# VisualightMicroDIY_034_gnd.net
KiCad netlist of a schematic drawn in EAGLE
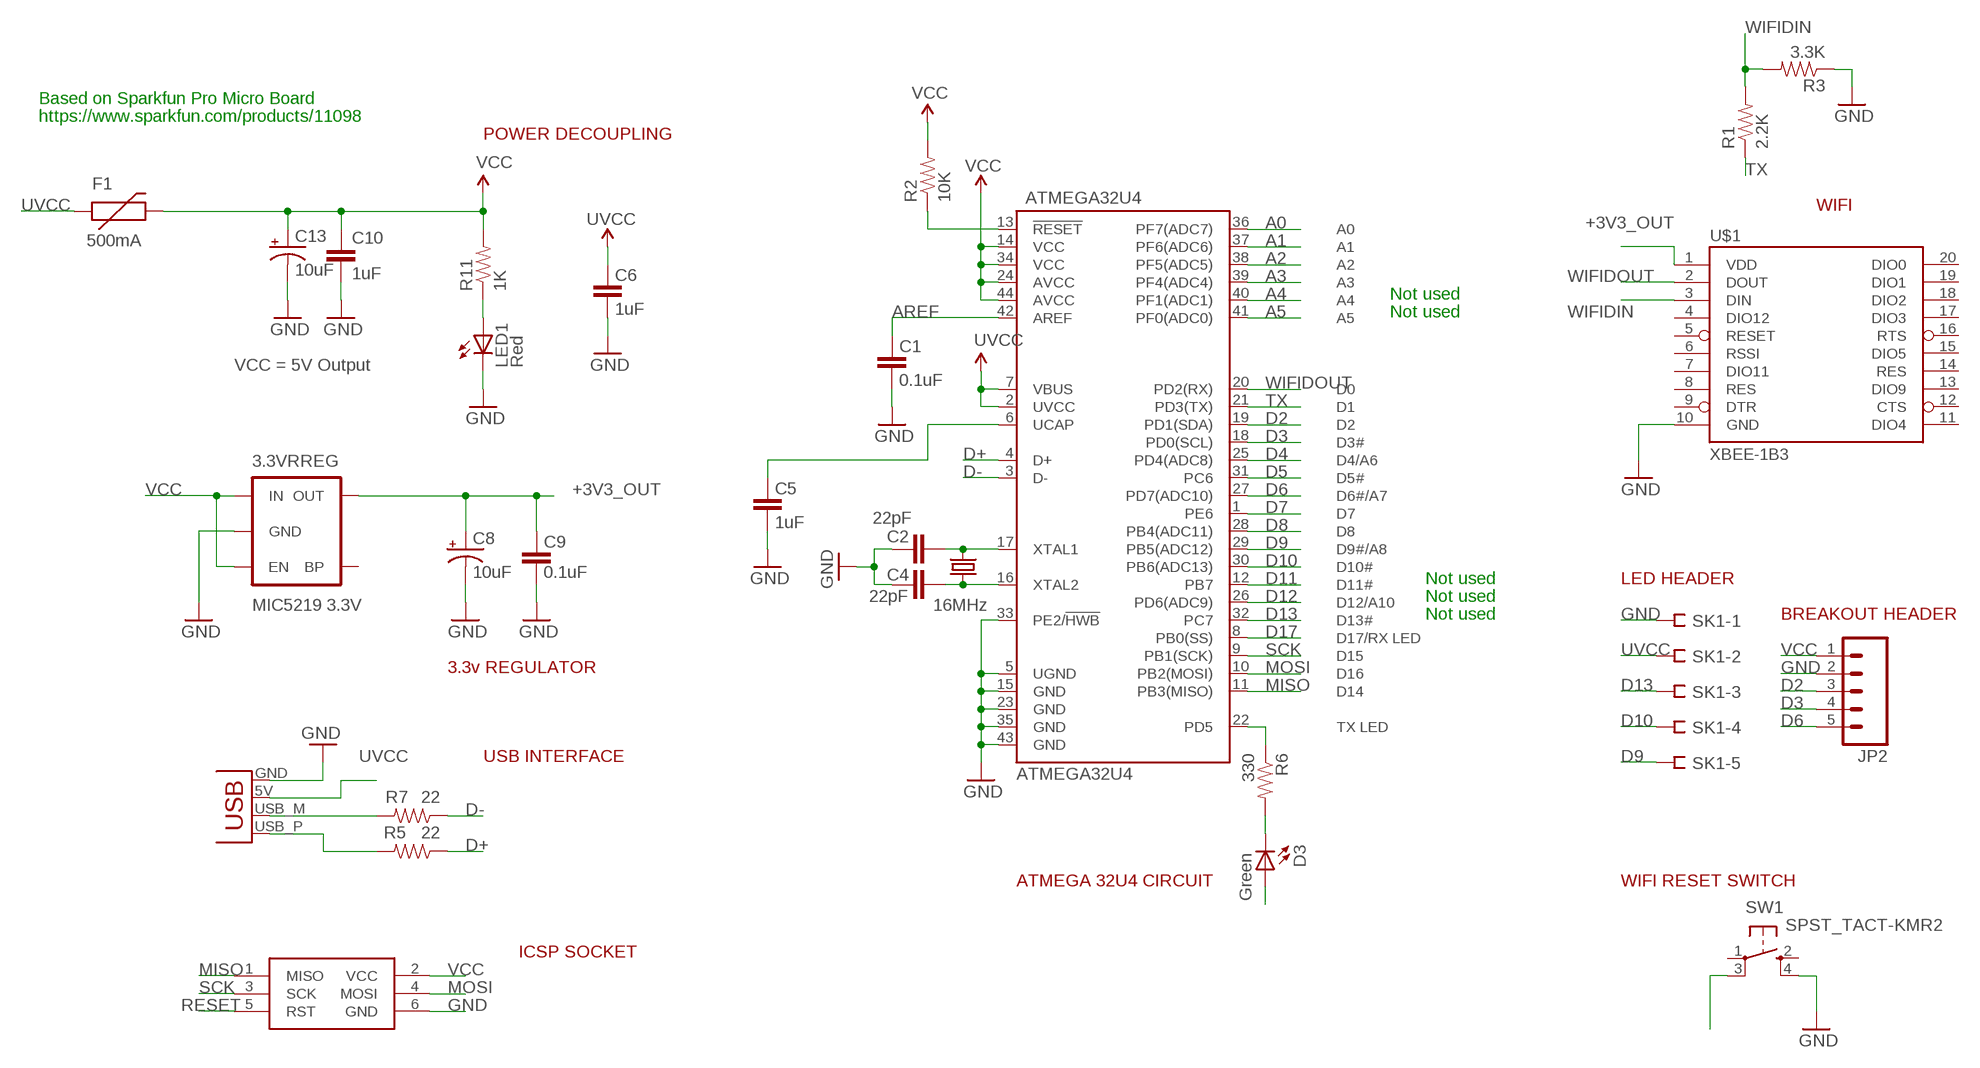
[diagram p0: schematic, sheet 1]

(export (version "E")
  (design (tool "Eeschema 10.0.6"))
  (components
    (comp (ref "3.3VRREG")
      (value "MIC5219 3.3V")
      (footprint "eagle-import:SOT23-5")
      (libsource (lib "eagle-import") (part "V_REG_MIC52193.3V"))
    )
    (comp (ref "ATMEGA32U4")
      (value "ATMEGA32U4")
      (footprint "eagle-import:SPARKFUN-DIGITALIC_TQFP44")
      (libsource (lib "eagle-import") (part "ATMEGA32U4TQFP"))
    )
    (comp (ref "C1")
      (value "0.1uF")
      (footprint "eagle-import:0402-CAP")
      (libsource (lib "eagle-import") (part "CAP0402-CAP"))
    )
    (comp (ref "C2")
      (value "22pF")
      (footprint "eagle-import:0402-CAP")
      (libsource (lib "eagle-import") (part "CAP0402-CAP"))
    )
    (comp (ref "C4")
      (value "22pF")
      (footprint "eagle-import:0402-CAP")
      (libsource (lib "eagle-import") (part "CAP0402-CAP"))
    )
    (comp (ref "C5")
      (value "1uF")
      (footprint "eagle-import:0402-CAP")
      (libsource (lib "eagle-import") (part "CAP0402-CAP"))
    )
    (comp (ref "C6")
      (value "1uF")
      (footprint "eagle-import:0402-CAP")
      (libsource (lib "eagle-import") (part "CAP0402-CAP"))
    )
    (comp (ref "C8")
      (value "10uF")
      (footprint "eagle-import:EIA3216")
      (libsource (lib "eagle-import") (part "CAP_POL1206"))
    )
    (comp (ref "C9")
      (value "0.1uF")
      (footprint "eagle-import:0402-CAP")
      (libsource (lib "eagle-import") (part "CAP0402-CAP"))
    )
    (comp (ref "C10")
      (value "1uF")
      (footprint "eagle-import:0402-CAP")
      (libsource (lib "eagle-import") (part "CAP0402-CAP"))
    )
    (comp (ref "C13")
      (value "10uF")
      (footprint "eagle-import:EIA3216")
      (libsource (lib "eagle-import") (part "CAP_POL1206"))
    )
    (comp (ref "D3")
      (value "Green")
      (footprint "eagle-import:LED-0603")
      (libsource (lib "eagle-import") (part "LED0603"))
    )
    (comp (ref "F1")
      (value "500mA")
      (footprint "eagle-import:PTC-1206")
      (libsource (lib "eagle-import") (part "PTCSMD"))
    )
    (comp (ref "ISP1")
      (value "AVRISP-6")
      (footprint "eagle-import:AVRISP")
      (libsource (lib "eagle-import") (part "AVRISP-6"))
    )
    (comp (ref "JP2")
      (value "M05PTH")
      (footprint "eagle-import:1X05")
      (libsource (lib "eagle-import") (part "M05PTH"))
    )
    (comp (ref "LED1")
      (value "Red")
      (footprint "eagle-import:LED-0603")
      (libsource (lib "eagle-import") (part "LED0603"))
    )
    (comp (ref "R1")
      (value "2.2K")
      (footprint "eagle-import:0402-RES")
      (libsource (lib "eagle-import") (part "RESISTOR0402-RES"))
    )
    (comp (ref "R2")
      (value "10K")
      (footprint "eagle-import:0402-RES")
      (libsource (lib "eagle-import") (part "RESISTOR0402-RES"))
    )
    (comp (ref "R3")
      (value "3.3K")
      (footprint "eagle-import:0402-RES")
      (libsource (lib "eagle-import") (part "RESISTOR0402-RES"))
    )
    (comp (ref "R5")
      (value "22")
      (footprint "eagle-import:0402-RES")
      (libsource (lib "eagle-import") (part "RESISTOR0402-RES"))
    )
    (comp (ref "R6")
      (value "330")
      (footprint "eagle-import:0402-RES")
      (libsource (lib "eagle-import") (part "RESISTOR0402-RES"))
    )
    (comp (ref "R7")
      (value "22")
      (footprint "eagle-import:0402-RES")
      (libsource (lib "eagle-import") (part "RESISTOR0402-RES"))
    )
    (comp (ref "R11")
      (value "1K")
      (footprint "eagle-import:0402-RES")
      (libsource (lib "eagle-import") (part "RESISTOR0402-RES"))
    )
    (comp (ref "SK1")
      (value "DF3-05S")
      (footprint "eagle-import:DF3S-05")
      (libsource (lib "eagle-import") (part "DF3-05S"))
    )
    (comp (ref "SW1")
      (value "SPST_TACT-KMR2")
      (footprint "eagle-import:KMR2")
      (libsource (lib "eagle-import") (part "SPST_TACT-KMR2"))
    )
    (comp (ref "U$1")
      (value "XBEE-1B3")
      (footprint "eagle-import:XBEE-SMD")
      (libsource (lib "eagle-import") (part "XBEE-1B3"))
    )
    (comp (ref "X2")
      (value "USBPCB")
      (footprint "eagle-import:USB-A-PCB")
      (libsource (lib "eagle-import") (part "USBPCB"))
    )
    (comp (ref "Y1")
      (value "16MHz")
      (footprint "eagle-import:CRYSTAL-SMD-5X3")
      (libsource (lib "eagle-import") (part "CRYSTAL5X3"))
    )
  )
  (nets
    (net (code "1") (name "/+3V3_OUT") (class "Default")
      (node (ref "3.3VRREG") (pin "5") (pinfunction "OUT_5") (pintype "passive"))
      (node (ref "C8") (pin "A") (pinfunction "+_A") (pintype "passive"))
      (node (ref "C9") (pin "2") (pinfunction "2_2") (pintype "passive"))
      (node (ref "U$1") (pin "1") (pinfunction "VDD_1") (pintype "power_in"))
    )
    (net (code "2") (name "/A0") (class "Default")
      (node (ref "ATMEGA32U4") (pin "36") (pinfunction "PF7(ADC7)_36") (pintype "bidirectional"))
    )
    (net (code "3") (name "/A1") (class "Default")
      (node (ref "ATMEGA32U4") (pin "37") (pinfunction "PF6(ADC6)_37") (pintype "bidirectional"))
    )
    (net (code "4") (name "/A2") (class "Default")
      (node (ref "ATMEGA32U4") (pin "38") (pinfunction "PF5(ADC5)_38") (pintype "bidirectional"))
    )
    (net (code "5") (name "/A3") (class "Default")
      (node (ref "ATMEGA32U4") (pin "39") (pinfunction "PF4(ADC4)_39") (pintype "bidirectional"))
    )
    (net (code "6") (name "/A4") (class "Default")
      (node (ref "ATMEGA32U4") (pin "40") (pinfunction "PF1(ADC1)_40") (pintype "bidirectional"))
    )
    (net (code "7") (name "/A5") (class "Default")
      (node (ref "ATMEGA32U4") (pin "41") (pinfunction "PF0(ADC0)_41") (pintype "bidirectional"))
    )
    (net (code "8") (name "/AREF") (class "Default")
      (node (ref "ATMEGA32U4") (pin "42") (pinfunction "AREF_42") (pintype "bidirectional"))
      (node (ref "C1") (pin "2") (pinfunction "2_2") (pintype "passive"))
    )
    (net (code "9") (name "/D+") (class "Default")
      (node (ref "ATMEGA32U4") (pin "4") (pinfunction "D+_4") (pintype "bidirectional"))
      (node (ref "R5") (pin "1") (pinfunction "1_1") (pintype "passive"))
    )
    (net (code "10") (name "/D-") (class "Default")
      (node (ref "ATMEGA32U4") (pin "3") (pinfunction "D-_3") (pintype "bidirectional"))
      (node (ref "R7") (pin "1") (pinfunction "1_1") (pintype "passive"))
    )
    (net (code "11") (name "/D2") (class "Default")
      (node (ref "ATMEGA32U4") (pin "19") (pinfunction "PD1(SDA)_19") (pintype "bidirectional"))
      (node (ref "JP2") (pin "3") (pinfunction "3_3") (pintype "passive"))
    )
    (net (code "12") (name "/D3") (class "Default")
      (node (ref "ATMEGA32U4") (pin "18") (pinfunction "PD0(SCL)_18") (pintype "bidirectional"))
      (node (ref "JP2") (pin "4") (pinfunction "4_4") (pintype "passive"))
    )
    (net (code "13") (name "/D4") (class "Default")
      (node (ref "ATMEGA32U4") (pin "25") (pinfunction "PD4(ADC8)_25") (pintype "bidirectional"))
    )
    (net (code "14") (name "/D5") (class "Default")
      (node (ref "ATMEGA32U4") (pin "31") (pinfunction "PC6_31") (pintype "bidirectional"))
    )
    (net (code "15") (name "/D6") (class "Default")
      (node (ref "ATMEGA32U4") (pin "27") (pinfunction "PD7(ADC10)_27") (pintype "bidirectional"))
      (node (ref "JP2") (pin "5") (pinfunction "5_5") (pintype "passive"))
    )
    (net (code "16") (name "/D7") (class "Default")
      (node (ref "ATMEGA32U4") (pin "1") (pinfunction "PE6_1") (pintype "bidirectional"))
      (node (ref "SW1") (pin "3") (pinfunction "P1_3") (pintype "passive"))
    )
    (net (code "17") (name "/D8") (class "Default")
      (node (ref "ATMEGA32U4") (pin "28") (pinfunction "PB4(ADC11)_28") (pintype "bidirectional"))
    )
    (net (code "18") (name "/D9") (class "Default")
      (node (ref "ATMEGA32U4") (pin "29") (pinfunction "PB5(ADC12)_29") (pintype "bidirectional"))
      (node (ref "SK1") (pin "5") (pinfunction "S_5") (pintype "passive"))
    )
    (net (code "19") (name "/D10") (class "Default")
      (node (ref "ATMEGA32U4") (pin "30") (pinfunction "PB6(ADC13)_30") (pintype "bidirectional"))
      (node (ref "SK1") (pin "4") (pinfunction "S_4") (pintype "passive"))
    )
    (net (code "20") (name "/D11") (class "Default")
      (node (ref "ATMEGA32U4") (pin "12") (pinfunction "PB7_12") (pintype "bidirectional"))
    )
    (net (code "21") (name "/D12") (class "Default")
      (node (ref "ATMEGA32U4") (pin "26") (pinfunction "PD6(ADC9)_26") (pintype "bidirectional"))
    )
    (net (code "22") (name "/D13") (class "Default")
      (node (ref "ATMEGA32U4") (pin "32") (pinfunction "PC7_32") (pintype "bidirectional"))
      (node (ref "SK1") (pin "3") (pinfunction "S_3") (pintype "passive"))
    )
    (net (code "23") (name "/D17") (class "Default")
      (node (ref "ATMEGA32U4") (pin "8") (pinfunction "PB0(SS)_8") (pintype "bidirectional"))
    )
    (net (code "24") (name "/MISO") (class "Default")
      (node (ref "ATMEGA32U4") (pin "11") (pinfunction "PB3(MISO)_11") (pintype "bidirectional"))
      (node (ref "ISP1") (pin "1") (pinfunction "MISO_1") (pintype "input"))
    )
    (net (code "25") (name "/MOSI") (class "Default")
      (node (ref "ATMEGA32U4") (pin "10") (pinfunction "PB2(MOSI)_10") (pintype "bidirectional"))
      (node (ref "ISP1") (pin "4") (pinfunction "MOSI_4") (pintype "output"))
    )
    (net (code "26") (name "/RESET") (class "Default")
      (node (ref "ATMEGA32U4") (pin "13") (pinfunction "~{RESET}_13") (pintype "bidirectional"))
      (node (ref "ISP1") (pin "5") (pinfunction "RST_5") (pintype "output"))
      (node (ref "R2") (pin "1") (pinfunction "1_1") (pintype "passive"))
    )
    (net (code "27") (name "/SCK") (class "Default")
      (node (ref "ATMEGA32U4") (pin "9") (pinfunction "PB1(SCK)_9") (pintype "bidirectional"))
      (node (ref "ISP1") (pin "3") (pinfunction "SCK_3") (pintype "output"))
    )
    (net (code "28") (name "/TX") (class "Default")
      (node (ref "ATMEGA32U4") (pin "21") (pinfunction "PD3(TX)_21") (pintype "bidirectional"))
      (node (ref "R1") (pin "1") (pinfunction "1_1") (pintype "passive"))
    )
    (net (code "29") (name "/WIFIDIN") (class "Default")
      (node (ref "R1") (pin "2") (pinfunction "2_2") (pintype "passive"))
      (node (ref "R3") (pin "2") (pinfunction "2_2") (pintype "passive"))
      (node (ref "U$1") (pin "3") (pinfunction "DIN_3") (pintype "input"))
    )
    (net (code "30") (name "/WIFIDOUT") (class "Default")
      (node (ref "ATMEGA32U4") (pin "20") (pinfunction "PD2(RX)_20") (pintype "bidirectional"))
      (node (ref "U$1") (pin "2") (pinfunction "DOUT_2") (pintype "output"))
    )
    (net (code "31") (name "GND") (class "Default")
      (node (ref "3.3VRREG") (pin "2") (pinfunction "GND_2") (pintype "input"))
      (node (ref "ATMEGA32U4") (pin "15") (pinfunction "GND_15") (pintype "bidirectional"))
      (node (ref "ATMEGA32U4") (pin "23") (pinfunction "GND_23") (pintype "bidirectional"))
      (node (ref "ATMEGA32U4") (pin "33") (pinfunction "PE2/~{HWB}_33") (pintype "bidirectional"))
      (node (ref "ATMEGA32U4") (pin "35") (pinfunction "GND_35") (pintype "bidirectional"))
      (node (ref "ATMEGA32U4") (pin "43") (pinfunction "GND_43") (pintype "bidirectional"))
      (node (ref "ATMEGA32U4") (pin "5") (pinfunction "UGND_5") (pintype "bidirectional"))
      (node (ref "C1") (pin "1") (pinfunction "1_1") (pintype "passive"))
      (node (ref "C10") (pin "2") (pinfunction "2_2") (pintype "passive"))
      (node (ref "C13") (pin "C") (pinfunction "-_C") (pintype "passive"))
      (node (ref "C2") (pin "2") (pinfunction "2_2") (pintype "passive"))
      (node (ref "C4") (pin "2") (pinfunction "2_2") (pintype "passive"))
      (node (ref "C5") (pin "1") (pinfunction "1_1") (pintype "passive"))
      (node (ref "C6") (pin "1") (pinfunction "1_1") (pintype "passive"))
      (node (ref "C8") (pin "C") (pinfunction "-_C") (pintype "passive"))
      (node (ref "C9") (pin "1") (pinfunction "1_1") (pintype "passive"))
      (node (ref "ISP1") (pin "6") (pinfunction "GND_6") (pintype "power_in"))
      (node (ref "JP2") (pin "2") (pinfunction "2_2") (pintype "passive"))
      (node (ref "LED1") (pin "C") (pinfunction "C_C") (pintype "passive"))
      (node (ref "R3") (pin "1") (pinfunction "1_1") (pintype "passive"))
      (node (ref "SK1") (pin "1") (pinfunction "S_1") (pintype "passive"))
      (node (ref "SW1") (pin "4") (pinfunction "S1_4") (pintype "passive"))
      (node (ref "U$1") (pin "10") (pinfunction "GND_10") (pintype "power_in"))
      (node (ref "X2") (pin "GND") (pinfunction "GND_GND") (pintype "bidirectional"))
    )
    (net (code "32") (name "Net-(ATMEGA32U4-PD5)") (class "Default")
      (node (ref "ATMEGA32U4") (pin "22") (pinfunction "PD5_22") (pintype "bidirectional"))
      (node (ref "R6") (pin "1") (pinfunction "1_1") (pintype "passive"))
    )
    (net (code "33") (name "Net-(ATMEGA32U4-UCAP)") (class "Default")
      (node (ref "ATMEGA32U4") (pin "6") (pinfunction "UCAP_6") (pintype "bidirectional"))
      (node (ref "C5") (pin "2") (pinfunction "2_2") (pintype "passive"))
    )
    (net (code "34") (name "Net-(ATMEGA32U4-XTAL1)") (class "Default")
      (node (ref "ATMEGA32U4") (pin "17") (pinfunction "XTAL1_17") (pintype "bidirectional"))
      (node (ref "C2") (pin "1") (pinfunction "1_1") (pintype "passive"))
      (node (ref "Y1") (pin "3") (pinfunction "2_3") (pintype "passive"))
    )
    (net (code "35") (name "Net-(ATMEGA32U4-XTAL2)") (class "Default")
      (node (ref "ATMEGA32U4") (pin "16") (pinfunction "XTAL2_16") (pintype "bidirectional"))
      (node (ref "C4") (pin "1") (pinfunction "1_1") (pintype "passive"))
      (node (ref "Y1") (pin "1") (pinfunction "1_1") (pintype "passive"))
    )
    (net (code "36") (name "Net-(D3-PadC)") (class "Default")
      (node (ref "D3") (pin "C") (pinfunction "C_C") (pintype "passive"))
      (node (ref "R6") (pin "2") (pinfunction "2_2") (pintype "passive"))
    )
    (net (code "37") (name "Net-(LED1-PadA)") (class "Default")
      (node (ref "LED1") (pin "A") (pinfunction "A_A") (pintype "passive"))
      (node (ref "R11") (pin "1") (pinfunction "1_1") (pintype "passive"))
    )
    (net (code "38") (name "Net-(X2-D+)") (class "Default")
      (node (ref "R5") (pin "2") (pinfunction "2_2") (pintype "passive"))
      (node (ref "X2") (pin "USB_P") (pinfunction "D+_USB_P") (pintype "bidirectional"))
    )
    (net (code "39") (name "Net-(X2-D-)") (class "Default")
      (node (ref "R7") (pin "2") (pinfunction "2_2") (pintype "passive"))
      (node (ref "X2") (pin "USB_M") (pinfunction "D-_USB_M") (pintype "bidirectional"))
    )
    (net (code "40") (name "UVCC") (class "Default")
      (node (ref "ATMEGA32U4") (pin "2") (pinfunction "UVCC_2") (pintype "bidirectional"))
      (node (ref "ATMEGA32U4") (pin "7") (pinfunction "VBUS_7") (pintype "bidirectional"))
      (node (ref "C6") (pin "2") (pinfunction "2_2") (pintype "passive"))
      (node (ref "F1") (pin "1") (pinfunction "1_1") (pintype "bidirectional"))
      (node (ref "SK1") (pin "2") (pinfunction "S_2") (pintype "passive"))
      (node (ref "X2") (pin "5V") (pinfunction "VBUS_5V") (pintype "bidirectional"))
    )
    (net (code "41") (name "VCC") (class "Default")
      (node (ref "3.3VRREG") (pin "1") (pinfunction "IN_1") (pintype "input"))
      (node (ref "3.3VRREG") (pin "3") (pinfunction "EN_3") (pintype "input"))
      (node (ref "ATMEGA32U4") (pin "14") (pinfunction "VCC_14") (pintype "bidirectional"))
      (node (ref "ATMEGA32U4") (pin "24") (pinfunction "AVCC_24") (pintype "bidirectional"))
      (node (ref "ATMEGA32U4") (pin "34") (pinfunction "VCC_34") (pintype "bidirectional"))
      (node (ref "ATMEGA32U4") (pin "44") (pinfunction "AVCC_44") (pintype "bidirectional"))
      (node (ref "C10") (pin "1") (pinfunction "1_1") (pintype "passive"))
      (node (ref "C13") (pin "A") (pinfunction "+_A") (pintype "passive"))
      (node (ref "D3") (pin "A") (pinfunction "A_A") (pintype "passive"))
      (node (ref "F1") (pin "2") (pinfunction "2_2") (pintype "bidirectional"))
      (node (ref "ISP1") (pin "2") (pinfunction "VCC_2") (pintype "power_in"))
      (node (ref "JP2") (pin "1") (pinfunction "1_1") (pintype "passive"))
      (node (ref "R11") (pin "2") (pinfunction "2_2") (pintype "passive"))
      (node (ref "R2") (pin "2") (pinfunction "2_2") (pintype "passive"))
    )
    (net (code "42") (name "unconnected-(3.3VRREG-BP-Pad4)") (class "Default")
      (node (ref "3.3VRREG") (pin "4") (pinfunction "BP_4") (pintype "input"))
    )
    (net (code "43") (name "unconnected-(SW1-P-Pad1)") (class "Default")
      (node (ref "SW1") (pin "1") (pinfunction "P_1") (pintype "passive"))
    )
    (net (code "44") (name "unconnected-(SW1-S-Pad2)") (class "Default")
      (node (ref "SW1") (pin "2") (pinfunction "S_2") (pintype "passive"))
    )
    (net (code "45") (name "unconnected-(U$1-CTS-Pad12)") (class "Default")
      (node (ref "U$1") (pin "12") (pinfunction "CTS_12") (pintype "output"))
    )
    (net (code "46") (name "unconnected-(U$1-DIO0-Pad20)") (class "Default")
      (node (ref "U$1") (pin "20") (pinfunction "DIO0_20") (pintype "bidirectional"))
    )
    (net (code "47") (name "unconnected-(U$1-DIO1-Pad19)") (class "Default")
      (node (ref "U$1") (pin "19") (pinfunction "DIO1_19") (pintype "bidirectional"))
    )
    (net (code "48") (name "unconnected-(U$1-DIO2-Pad18)") (class "Default")
      (node (ref "U$1") (pin "18") (pinfunction "DIO2_18") (pintype "bidirectional"))
    )
    (net (code "49") (name "unconnected-(U$1-DIO3-Pad17)") (class "Default")
      (node (ref "U$1") (pin "17") (pinfunction "DIO3_17") (pintype "bidirectional"))
    )
    (net (code "50") (name "unconnected-(U$1-DIO4-Pad11)") (class "Default")
      (node (ref "U$1") (pin "11") (pinfunction "DIO4_11") (pintype "bidirectional"))
    )
    (net (code "51") (name "unconnected-(U$1-DIO5-Pad15)") (class "Default")
      (node (ref "U$1") (pin "15") (pinfunction "DIO5_15") (pintype "bidirectional"))
    )
    (net (code "52") (name "unconnected-(U$1-DIO9-Pad13)") (class "Default")
      (node (ref "U$1") (pin "13") (pinfunction "DIO9_13") (pintype "bidirectional"))
    )
    (net (code "53") (name "unconnected-(U$1-DIO11-Pad7)") (class "Default")
      (node (ref "U$1") (pin "7") (pinfunction "DIO11_7") (pintype "bidirectional"))
    )
    (net (code "54") (name "unconnected-(U$1-DIO12-Pad4)") (class "Default")
      (node (ref "U$1") (pin "4") (pinfunction "DIO12_4") (pintype "bidirectional"))
    )
    (net (code "55") (name "unconnected-(U$1-DTR-Pad9)") (class "Default")
      (node (ref "U$1") (pin "9") (pinfunction "DTR_9") (pintype "bidirectional"))
    )
    (net (code "56") (name "unconnected-(U$1-RES-Pad8)") (class "Default")
      (node (ref "U$1") (pin "8") (pinfunction "RES_8") (pintype "bidirectional"))
    )
    (net (code "57") (name "unconnected-(U$1-RES-Pad14)") (class "Default")
      (node (ref "U$1") (pin "14") (pinfunction "RES_14") (pintype "bidirectional"))
    )
    (net (code "58") (name "unconnected-(U$1-RESET-Pad5)") (class "Default")
      (node (ref "U$1") (pin "5") (pinfunction "RESET_5") (pintype "input"))
    )
    (net (code "59") (name "unconnected-(U$1-RSSI-Pad6)") (class "Default")
      (node (ref "U$1") (pin "6") (pinfunction "RSSI_6") (pintype "bidirectional"))
    )
    (net (code "60") (name "unconnected-(U$1-RTS-Pad16)") (class "Default")
      (node (ref "U$1") (pin "16") (pinfunction "RTS_16") (pintype "input"))
    )
  )
)
